# Carduino.net
KiCad netlist of a schematic drawn in Altium Designer
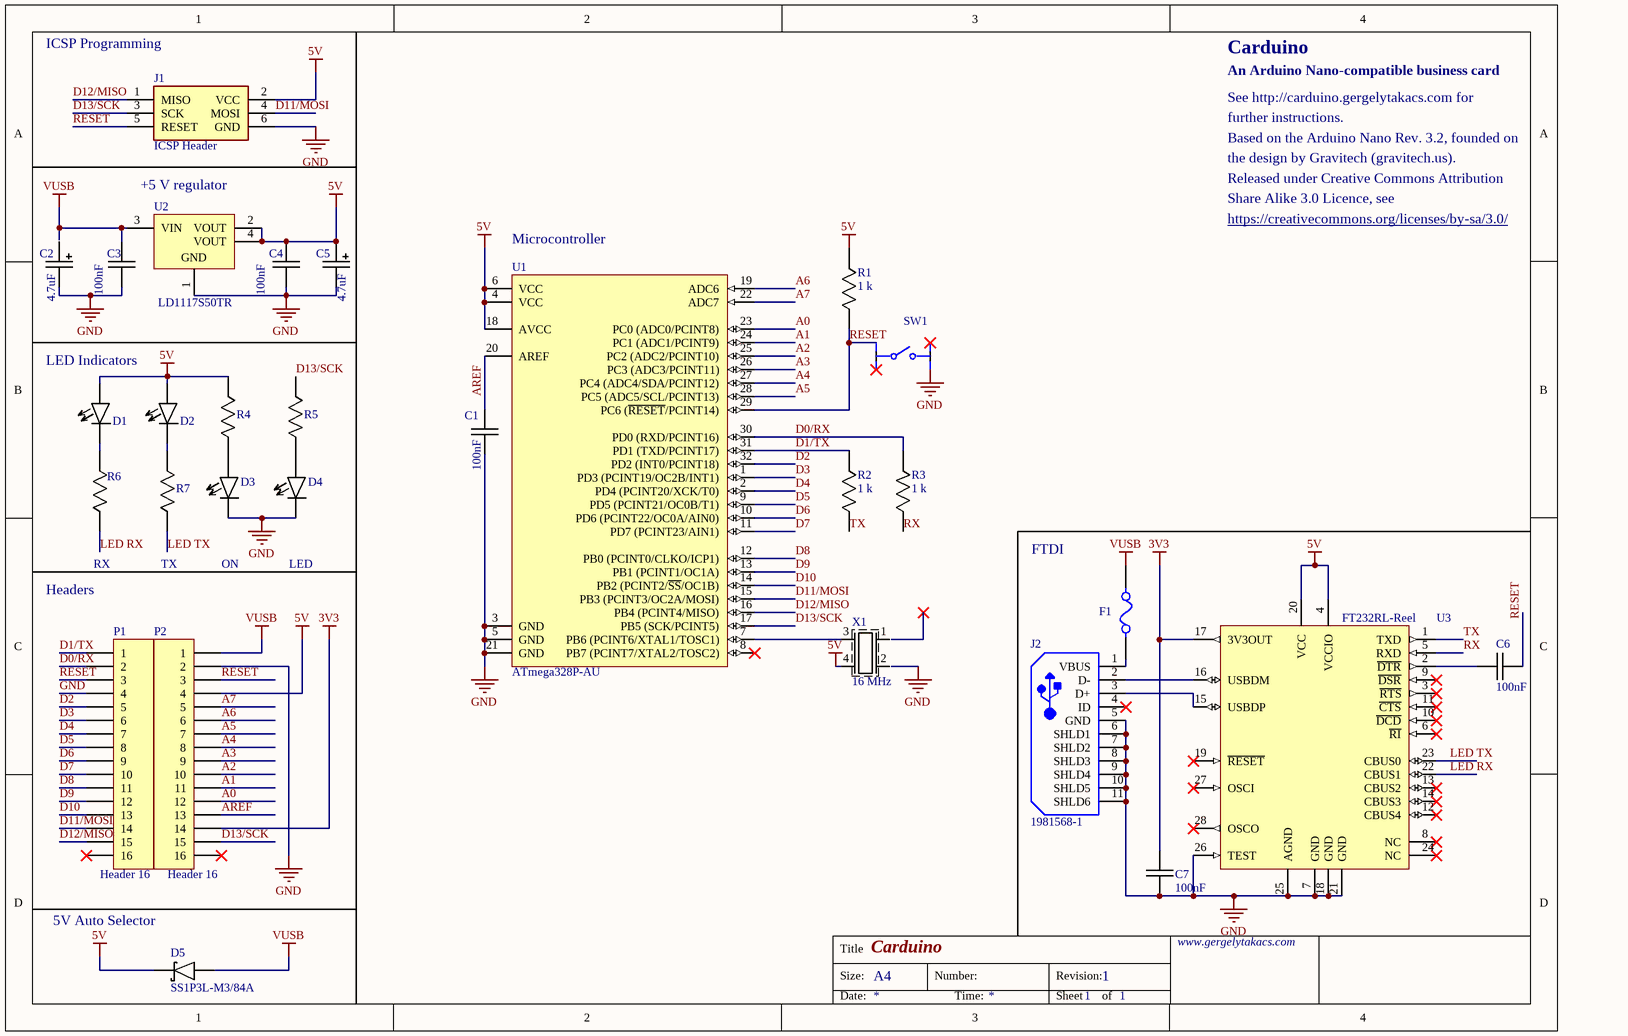
[diagram p0: Carduino.SchDoc]

(export (version "E")
  (design (tool "Eeschema 10.0.6"))
  (components
    (comp (ref "C1")
      (value "100nF")
      (footprint "CAPC2013X09N")
      (description "Ceramic condenser MLCC; 100nF; 25V; X7R; ±10%; SMD; 0805")
      (libsource (lib "Capacitors") (part "100 uF,  ceramic, 0805, Kemet"))
    )
    (comp (ref "C2")
      (value "4.7uF")
      (footprint "CAP body B")
      (description "4,7uF; 25VDC; SMD; Puzd: B; ±10%; -55÷125°C")
      (libsource (lib "Capacitors") (part "4.7uF, Tantallum"))
    )
    (comp (ref "C3")
      (value "100nF")
      (footprint "CAPC2013X09N")
      (description "Ceramic condenser MLCC; 100nF; 25V; X7R; ±10%; SMD; 0805")
      (libsource (lib "Capacitors") (part "100 uF,  ceramic, 0805, Kemet"))
    )
    (comp (ref "C4")
      (value "100nF")
      (footprint "CAPC2013X09N")
      (description "Ceramic condenser MLCC; 100nF; 25V; X7R; ±10%; SMD; 0805")
      (libsource (lib "Capacitors") (part "100 uF,  ceramic, 0805, Kemet"))
    )
    (comp (ref "C5")
      (value "4.7uF")
      (footprint "CAP body B")
      (description "4,7uF; 25VDC; SMD; Puzd: B; ±10%; -55÷125°C")
      (libsource (lib "Capacitors") (part "4.7uF, Tantallum"))
    )
    (comp (ref "C6")
      (value "100nF")
      (footprint "CAPC2013X09N")
      (description "Ceramic condenser MLCC; 100nF; 25V; X7R; ±10%; SMD; 0805")
      (libsource (lib "Capacitors") (part "100 uF,  ceramic, 0805, Kemet"))
    )
    (comp (ref "C7")
      (value "100nF")
      (footprint "CAPC2013X09N")
      (description "Ceramic condenser MLCC; 100nF; 25V; X7R; ±10%; SMD; 0805")
      (libsource (lib "Capacitors") (part "100 uF,  ceramic, 0805, Kemet"))
    )
    (comp (ref "D1")
      (value "OSXX0805C1E")
      (footprint "DIOC2012X09N")
      (description "OptoSupply Single Chip LED 0805")
      (fields
        (field (name "CREATOR") "Gergely Takacs")
        (field (name "CREATOR WWW") "http://www.gergelytakacs.com")
      )
      (libsource (lib "OptoSupplyLED") (part "OptoSupply RED"))
    )
    (comp (ref "D2")
      (value "OSXX0805C1E")
      (footprint "DIOC2012X09N")
      (description "OptoSupply Single Chip LED 0805")
      (fields
        (field (name "CREATOR") "Gergely Takacs")
        (field (name "CREATOR WWW") "http://www.gergelytakacs.com")
      )
      (libsource (lib "OptoSupplyLED") (part "OptoSupply RED"))
    )
    (comp (ref "D3")
      (value "OSXX0805C1E")
      (footprint "DIOC2012X09N")
      (description "OptoSupply Single Chip LED 0805")
      (fields
        (field (name "CREATOR") "Gergely Takacs")
        (field (name "CREATOR WWW") "http://www.gergelytakacs.com")
      )
      (libsource (lib "OptoSupplyLED") (part "OptoSupply RED"))
    )
    (comp (ref "D4")
      (value "OSXX0805C1E")
      (footprint "DIOC2012X09N")
      (description "OptoSupply Single Chip LED 0805")
      (fields
        (field (name "CREATOR") "Gergely Takacs")
        (field (name "CREATOR WWW") "http://www.gergelytakacs.com")
      )
      (libsource (lib "OptoSupplyLED") (part "OptoSupply RED"))
    )
    (comp (ref "D5")
      (value "SS1P3L-M3/84A")
      (footprint "DIOM3420X11N")
      (description "VISHAY SS1P3L-M3/84A  Dióda: usmerňovacia Schottky; SMD; 30V; 1A; DO220AA, SMP")
      (libsource (lib "Diodes") (part "SS1P3L"))
    )
    (comp (ref "F1")
      (value "ECE SR050-06")
      (footprint "RESC2113X12N")
      (description "FUSE PTC RESETTABLE .50A")
      (libsource (lib "Fuses") (part "ECE SR050-06"))
    )
    (comp (ref "J1")
      (value "Conn_3M_961206-6404-AR_eec")
      (footprint "3M_961206-6404-AR_0")
      (description "CONN HEADER VERT DUAL 6POS GOLD")
      (fields
        (field (name "MANUFACTURER") "3M")
        (field (name "MOUSER PART NUMBER") "517-9612066404AR")
        (field (name "PART NUMBER") "ICSP Header")
      )
      (libsource (lib "ICSP") (part "Conn_3M_961206-6404-AR_eec"))
    )
    (comp (ref "J2")
      (value "1981568-1")
      (footprint "TECO-1981568-5_V")
      (description "Micro USB Receptacle Standard Type B Assy, 5-Pin SMD, RoHS, Tape and Reel")
      (fields (field (name "MANUFACTURER") "TE Connectivity"))
      (libsource (lib "Connectors") (part "1981568-1"))
    )
    (comp (ref "P1")
      (value "Header 16")
      (footprint "HDR1X16")
      (description "Header, 16-Pin")
      (fields (field (name "PUBLISHER") "Altium Limited"))
      (libsource (lib "Miscellaneous Connectors") (part "Header 16"))
    )
    (comp (ref "P2")
      (value "Header 16")
      (footprint "HDR1X16")
      (description "Header, 16-Pin")
      (fields (field (name "PUBLISHER") "Altium Limited"))
      (libsource (lib "") (part "Header 16_1"))
    )
    (comp (ref "R1")
      (value "1 k")
      (footprint "RESC2112X05N")
      (description "ROYAL OHM HP05W3F1001T5E  Rezistor: thick film; vysokovýkonný; SMD; 0805; 1kΩ; 0,3W; ±1%")
      (libsource (lib "Resistors") (part "1k, 0805, Royal Ohm"))
    )
    (comp (ref "R2")
      (value "1 k")
      (footprint "RESC2112X05N")
      (description "ROYAL OHM HP05W3F1001T5E  Rezistor: thick film; vysokovýkonný; SMD; 0805; 1kΩ; 0,3W; ±1%")
      (libsource (lib "Resistors") (part "1k, 0805, Royal Ohm"))
    )
    (comp (ref "R3")
      (value "1 k")
      (footprint "RESC2112X05N")
      (description "ROYAL OHM HP05W3F1001T5E  Rezistor: thick film; vysokovýkonný; SMD; 0805; 1kΩ; 0,3W; ±1%")
      (libsource (lib "Resistors") (part "1k, 0805, Royal Ohm"))
    )
    (comp (ref "R4")
      (value "270 Ohm, 0805")
      (footprint "RESC2112X05N")
      (description "VISHAY CRCW...BC Thick Film Commodity Resistor")
      (libsource (lib "Vishay Resistors") (part "270 Ohm, 0805, Resistor"))
    )
    (comp (ref "R5")
      (value "270 Ohm, 0805")
      (footprint "RESC2112X05N")
      (description "VISHAY CRCW...BC Thick Film Commodity Resistor")
      (libsource (lib "Vishay Resistors") (part "270 Ohm, 0805, Resistor"))
    )
    (comp (ref "R6")
      (value "270 Ohm, 0805")
      (footprint "RESC2112X05N")
      (description "VISHAY CRCW...BC Thick Film Commodity Resistor")
      (libsource (lib "Vishay Resistors") (part "270 Ohm, 0805, Resistor"))
    )
    (comp (ref "R7")
      (value "270 Ohm, 0805")
      (footprint "RESC2112X05N")
      (description "VISHAY CRCW...BC Thick Film Commodity Resistor")
      (libsource (lib "Vishay Resistors") (part "270 Ohm, 0805, Resistor"))
    )
    (comp (ref "SW1")
      (value "Switch_TE_1825910-7_eec")
      (footprint "TE_1825910-7_0")
      (description "SWITCH Tactile Switch SPST-NO Top Actuated Through Hole")
      (fields (field (name "PART NUMBER") "1825910-7") (field (name "MANUFACTURER") "TE"))
      (libsource (lib "Switches") (part "Switch_TE_1825910-7_eec"))
    )
    (comp (ref "U1")
      (value "ATmega328P-AU")
      (footprint "32A_N")
      (libsource (lib "Atmel Microcontroller megaAVR") (part "ATmega328P-AU"))
    )
    (comp (ref "U2")
      (value "LD1117S50TR")
      (footprint "SOT-223_N")
      (description "Fixed Low Drop Positive Voltage Regulator, 5V, 4-Pin SOT-223, Tape and Reel")
      (libsource (lib "STMicroelectronics Power Management Linear Regulator") (part "LD1117S50TR"))
    )
    (comp (ref "U3")
      (value "FT232RL-Reel")
      (footprint "SSOP-28_N")
      (description "USB UART Asynchronous Serial Data Transfer Chip, 28-pin SSOP, Tape and Reel")
      (fields (field (name "MANUFACTURER") "FTDI"))
      (libsource (lib "FTDI FT Series") (part "FT232RL-Reel"))
    )
    (comp (ref "X1")
      (value "16 MHz")
      (footprint "DFN598P720X140-4N")
      (description "QD FREQUENCY PRODUCTS LF SPXO018034")
      (libsource (lib "Xtals") (part "16 MHz, IQD FREQUENCY PRODUCTS"))
    )
  )
  (nets
    (net (code "1") (name "/A0") (class "Default")
      (node (ref "P2") (pin "12") (pinfunction "12_12") (pintype "passive"))
      (node (ref "U1") (pin "23") (pinfunction "PC0_(ADC0/PCINT8)_23") (pintype "bidirectional"))
    )
    (net (code "2") (name "/A1") (class "Default")
      (node (ref "P2") (pin "11") (pinfunction "11_11") (pintype "passive"))
      (node (ref "U1") (pin "24") (pinfunction "PC1_(ADC1/PCINT9)_24") (pintype "bidirectional"))
    )
    (net (code "3") (name "/A2") (class "Default")
      (node (ref "P2") (pin "10") (pinfunction "10_10") (pintype "passive"))
      (node (ref "U1") (pin "25") (pinfunction "PC2_(ADC2/PCINT10)_25") (pintype "bidirectional"))
    )
    (net (code "4") (name "/A3") (class "Default")
      (node (ref "P2") (pin "9") (pinfunction "9_9") (pintype "passive"))
      (node (ref "U1") (pin "26") (pinfunction "PC3_(ADC3/PCINT11)_26") (pintype "bidirectional"))
    )
    (net (code "5") (name "/A4") (class "Default")
      (node (ref "P2") (pin "8") (pinfunction "8_8") (pintype "passive"))
      (node (ref "U1") (pin "27") (pinfunction "PC4_(ADC4/SDA/PCINT12)_27") (pintype "bidirectional"))
    )
    (net (code "6") (name "/A5") (class "Default")
      (node (ref "P2") (pin "7") (pinfunction "7_7") (pintype "passive"))
      (node (ref "U1") (pin "28") (pinfunction "PC5_(ADC5/SCL/PCINT13)_28") (pintype "bidirectional"))
    )
    (net (code "7") (name "/A6") (class "Default")
      (node (ref "P2") (pin "6") (pinfunction "6_6") (pintype "passive"))
      (node (ref "U1") (pin "19") (pinfunction "ADC6_19") (pintype "input"))
    )
    (net (code "8") (name "/A7") (class "Default")
      (node (ref "P2") (pin "5") (pinfunction "5_5") (pintype "passive"))
      (node (ref "U1") (pin "22") (pinfunction "ADC7_22") (pintype "input"))
    )
    (net (code "9") (name "/AREF") (class "Default")
      (node (ref "C1") (pin "1") (pinfunction "1_1") (pintype "passive"))
      (node (ref "P2") (pin "13") (pinfunction "13_13") (pintype "passive"))
      (node (ref "U1") (pin "20") (pinfunction "AREF_20") (pintype "passive"))
    )
    (net (code "10") (name "/D0{slash}RX") (class "Default")
      (node (ref "P1") (pin "2") (pinfunction "2_2") (pintype "passive"))
      (node (ref "R3") (pin "2") (pinfunction "2_2") (pintype "passive"))
      (node (ref "U1") (pin "30") (pinfunction "PD0_(RXD/PCINT16)_30") (pintype "bidirectional"))
    )
    (net (code "11") (name "/D1{slash}TX") (class "Default")
      (node (ref "P1") (pin "1") (pinfunction "1_1") (pintype "passive"))
      (node (ref "R2") (pin "1") (pinfunction "1_1") (pintype "passive"))
      (node (ref "U1") (pin "31") (pinfunction "PD1_(TXD/PCINT17)_31") (pintype "bidirectional"))
    )
    (net (code "12") (name "/D2") (class "Default")
      (node (ref "P1") (pin "5") (pinfunction "5_5") (pintype "passive"))
      (node (ref "U1") (pin "32") (pinfunction "PD2_(INT0/PCINT18)_32") (pintype "bidirectional"))
    )
    (net (code "13") (name "/D3") (class "Default")
      (node (ref "P1") (pin "6") (pinfunction "6_6") (pintype "passive"))
      (node (ref "U1") (pin "1") (pinfunction "PD3_(PCINT19/OC2B/INT1)_1") (pintype "bidirectional"))
    )
    (net (code "14") (name "/D4") (class "Default")
      (node (ref "P1") (pin "7") (pinfunction "7_7") (pintype "passive"))
      (node (ref "U1") (pin "2") (pinfunction "PD4_(PCINT20/XCK/T0)_2") (pintype "bidirectional"))
    )
    (net (code "15") (name "/D5") (class "Default")
      (node (ref "P1") (pin "8") (pinfunction "8_8") (pintype "passive"))
      (node (ref "U1") (pin "9") (pinfunction "PD5_(PCINT21/OC0B/T1)_9") (pintype "bidirectional"))
    )
    (net (code "16") (name "/D6") (class "Default")
      (node (ref "P1") (pin "9") (pinfunction "9_9") (pintype "passive"))
      (node (ref "U1") (pin "10") (pinfunction "PD6_(PCINT22/OC0A/AIN0)_10") (pintype "bidirectional"))
    )
    (net (code "17") (name "/D7") (class "Default")
      (node (ref "P1") (pin "10") (pinfunction "10_10") (pintype "passive"))
      (node (ref "U1") (pin "11") (pinfunction "PD7_(PCINT23/AIN1)_11") (pintype "bidirectional"))
    )
    (net (code "18") (name "/D8") (class "Default")
      (node (ref "P1") (pin "11") (pinfunction "11_11") (pintype "passive"))
      (node (ref "U1") (pin "12") (pinfunction "PB0_(PCINT0/CLKO/ICP1)_12") (pintype "bidirectional"))
    )
    (net (code "19") (name "/D9") (class "Default")
      (node (ref "P1") (pin "12") (pinfunction "12_12") (pintype "passive"))
      (node (ref "U1") (pin "13") (pinfunction "PB1_(PCINT1/OC1A)_13") (pintype "bidirectional"))
    )
    (net (code "20") (name "/D10") (class "Default")
      (node (ref "P1") (pin "13") (pinfunction "13_13") (pintype "passive"))
      (node (ref "U1") (pin "14") (pinfunction "PB2_(PCINT2/~{SS}/OC1B)_14") (pintype "bidirectional"))
    )
    (net (code "21") (name "/D11{slash}MOSI") (class "Default")
      (node (ref "J1") (pin "4") (pinfunction "MOSI_4") (pintype "passive"))
      (node (ref "P1") (pin "14") (pinfunction "14_14") (pintype "passive"))
      (node (ref "U1") (pin "15") (pinfunction "PB3_(PCINT3/OC2A/MOSI)_15") (pintype "bidirectional"))
    )
    (net (code "22") (name "/D12{slash}MISO") (class "Default")
      (node (ref "J1") (pin "1") (pinfunction "MISO_1") (pintype "passive"))
      (node (ref "P1") (pin "15") (pinfunction "15_15") (pintype "passive"))
      (node (ref "U1") (pin "16") (pinfunction "PB4_(PCINT4/MISO)_16") (pintype "bidirectional"))
    )
    (net (code "23") (name "/D13{slash}SCK") (class "Default")
      (node (ref "J1") (pin "3") (pinfunction "SCK_3") (pintype "passive"))
      (node (ref "P2") (pin "15") (pinfunction "15_15") (pintype "passive"))
      (node (ref "R5") (pin "1") (pinfunction "1_1") (pintype "passive"))
      (node (ref "U1") (pin "17") (pinfunction "PB5_(SCK/PCINT5)_17") (pintype "bidirectional"))
    )
    (net (code "24") (name "/LED RX") (class "Default")
      (node (ref "R6") (pin "2") (pinfunction "2_2") (pintype "passive"))
      (node (ref "U3") (pin "22") (pinfunction "CBUS1_22") (pintype "bidirectional"))
    )
    (net (code "25") (name "/LED TX") (class "Default")
      (node (ref "R7") (pin "2") (pinfunction "2_2") (pintype "passive"))
      (node (ref "U3") (pin "23") (pinfunction "CBUS0_23") (pintype "bidirectional"))
    )
    (net (code "26") (name "/RESET") (class "Default")
      (node (ref "C6") (pin "2") (pinfunction "2_2") (pintype "passive"))
      (node (ref "J1") (pin "5") (pinfunction "RESET_5") (pintype "passive"))
      (node (ref "P1") (pin "3") (pinfunction "3_3") (pintype "passive"))
      (node (ref "P2") (pin "3") (pinfunction "3_3") (pintype "passive"))
      (node (ref "R1") (pin "2") (pinfunction "2_2") (pintype "passive"))
      (node (ref "SW1") (pin "1") (pinfunction "1_1") (pintype "passive"))
      (node (ref "U1") (pin "29") (pinfunction "PC6_(~{RESET}/PCINT14)_29") (pintype "bidirectional"))
    )
    (net (code "27") (name "/RX") (class "Default")
      (node (ref "R3") (pin "1") (pinfunction "1_1") (pintype "passive"))
      (node (ref "U3") (pin "5") (pinfunction "RXD_5") (pintype "input"))
    )
    (net (code "28") (name "/TX") (class "Default")
      (node (ref "R2") (pin "2") (pinfunction "2_2") (pintype "passive"))
      (node (ref "U3") (pin "1") (pinfunction "TXD_1") (pintype "output"))
    )
    (net (code "29") (name "3V3") (class "Default")
      (node (ref "C7") (pin "2") (pinfunction "2_2") (pintype "passive"))
      (node (ref "P2") (pin "14") (pinfunction "14_14") (pintype "passive"))
      (node (ref "U3") (pin "17") (pinfunction "3V3OUT_17") (pintype "output"))
    )
    (net (code "30") (name "5V") (class "Default")
      (node (ref "C4") (pin "1") (pinfunction "1_1") (pintype "passive"))
      (node (ref "C5") (pin "1") (pinfunction "1_1") (pintype "passive"))
      (node (ref "D1") (pin "2") (pinfunction "2_2") (pintype "passive"))
      (node (ref "D2") (pin "2") (pinfunction "2_2") (pintype "passive"))
      (node (ref "D5") (pin "1") (pinfunction "1_1") (pintype "passive"))
      (node (ref "J1") (pin "2") (pinfunction "VCC_2") (pintype "passive"))
      (node (ref "P2") (pin "4") (pinfunction "4_4") (pintype "passive"))
      (node (ref "R1") (pin "1") (pinfunction "1_1") (pintype "passive"))
      (node (ref "R4") (pin "1") (pinfunction "1_1") (pintype "passive"))
      (node (ref "U1") (pin "18") (pinfunction "AVCC_18") (pintype "power_in"))
      (node (ref "U1") (pin "4") (pinfunction "VCC_4") (pintype "power_in"))
      (node (ref "U1") (pin "6") (pinfunction "VCC_6") (pintype "power_in"))
      (node (ref "U2") (pin "2") (pinfunction "VOUT_2") (pintype "power_in"))
      (node (ref "U2") (pin "4") (pinfunction "VOUT_4") (pintype "power_in"))
      (node (ref "U3") (pin "20") (pinfunction "VCC_20") (pintype "power_in"))
      (node (ref "U3") (pin "4") (pinfunction "VCCIO_4") (pintype "power_in"))
      (node (ref "X1") (pin "4") (pinfunction "4_4") (pintype "passive"))
    )
    (net (code "31") (name "GND") (class "Default")
      (node (ref "C1") (pin "2") (pinfunction "2_2") (pintype "passive"))
      (node (ref "C2") (pin "2") (pinfunction "2_2") (pintype "passive"))
      (node (ref "C3") (pin "1") (pinfunction "1_1") (pintype "passive"))
      (node (ref "C4") (pin "2") (pinfunction "2_2") (pintype "passive"))
      (node (ref "C5") (pin "2") (pinfunction "2_2") (pintype "passive"))
      (node (ref "C7") (pin "1") (pinfunction "1_1") (pintype "passive"))
      (node (ref "D3") (pin "1") (pinfunction "1_1") (pintype "passive"))
      (node (ref "D4") (pin "1") (pinfunction "1_1") (pintype "passive"))
      (node (ref "J1") (pin "6") (pinfunction "GND_6") (pintype "passive"))
      (node (ref "J2") (pin "10") (pinfunction "SHLD5_10") (pintype "passive"))
      (node (ref "J2") (pin "11") (pinfunction "SHLD6_11") (pintype "passive"))
      (node (ref "J2") (pin "5") (pinfunction "GND_5") (pintype "passive"))
      (node (ref "J2") (pin "6") (pinfunction "SHLD1_6") (pintype "passive"))
      (node (ref "J2") (pin "7") (pinfunction "SHLD2_7") (pintype "passive"))
      (node (ref "J2") (pin "8") (pinfunction "SHLD3_8") (pintype "passive"))
      (node (ref "J2") (pin "9") (pinfunction "SHLD4_9") (pintype "passive"))
      (node (ref "P1") (pin "4") (pinfunction "4_4") (pintype "passive"))
      (node (ref "P2") (pin "2") (pinfunction "2_2") (pintype "passive"))
      (node (ref "SW1") (pin "4") (pinfunction "4_4") (pintype "passive"))
      (node (ref "U1") (pin "21") (pinfunction "GND_21") (pintype "power_in"))
      (node (ref "U1") (pin "3") (pinfunction "GND_3") (pintype "power_in"))
      (node (ref "U1") (pin "5") (pinfunction "GND_5") (pintype "power_in"))
      (node (ref "U2") (pin "1") (pinfunction "GND_1") (pintype "power_in"))
      (node (ref "U3") (pin "18") (pinfunction "GND_18") (pintype "power_in"))
      (node (ref "U3") (pin "21") (pinfunction "GND_21") (pintype "power_in"))
      (node (ref "U3") (pin "25") (pinfunction "AGND_25") (pintype "power_in"))
      (node (ref "U3") (pin "26") (pinfunction "TEST_26") (pintype "input"))
      (node (ref "U3") (pin "7") (pinfunction "GND_7") (pintype "power_in"))
    )
    (net (code "32") (name "Net-(D1-Pad1)") (class "Default")
      (node (ref "D1") (pin "1") (pinfunction "1_1") (pintype "passive"))
      (node (ref "R6") (pin "1") (pinfunction "1_1") (pintype "passive"))
    )
    (net (code "33") (name "Net-(D2-Pad1)") (class "Default")
      (node (ref "D2") (pin "1") (pinfunction "1_1") (pintype "passive"))
      (node (ref "R7") (pin "1") (pinfunction "1_1") (pintype "passive"))
    )
    (net (code "34") (name "Net-(D3-Pad2)") (class "Default")
      (node (ref "D3") (pin "2") (pinfunction "2_2") (pintype "passive"))
      (node (ref "R4") (pin "2") (pinfunction "2_2") (pintype "passive"))
    )
    (net (code "35") (name "Net-(D4-Pad2)") (class "Default")
      (node (ref "D4") (pin "2") (pinfunction "2_2") (pintype "passive"))
      (node (ref "R5") (pin "2") (pinfunction "2_2") (pintype "passive"))
    )
    (net (code "36") (name "Net-(J2-D+)") (class "Default")
      (node (ref "J2") (pin "3") (pinfunction "D+_3") (pintype "passive"))
      (node (ref "U3") (pin "15") (pinfunction "USBDP_15") (pintype "bidirectional"))
    )
    (net (code "37") (name "Net-(J2-D-)") (class "Default")
      (node (ref "J2") (pin "2") (pinfunction "D-_2") (pintype "passive"))
      (node (ref "U3") (pin "16") (pinfunction "USBDM_16") (pintype "bidirectional"))
    )
    (net (code "38") (name "Net-(J2-VBUS)") (class "Default")
      (node (ref "F1") (pin "1") (pinfunction "1_1") (pintype "passive"))
      (node (ref "J2") (pin "1") (pinfunction "VBUS_1") (pintype "passive"))
    )
    (net (code "39") (name "Net-(U1-PB6_(PCINT6{slash}XTAL1{slash}TOSC1))") (class "Default")
      (node (ref "U1") (pin "7") (pinfunction "PB6_(PCINT6/XTAL1/TOSC1)_7") (pintype "bidirectional"))
      (node (ref "X1") (pin "3") (pinfunction "3_3") (pintype "passive"))
    )
    (net (code "40") (name "Net-(U3-~{DTR})") (class "Default")
      (node (ref "C6") (pin "1") (pinfunction "1_1") (pintype "passive"))
      (node (ref "U3") (pin "2") (pinfunction "~{DTR}_2") (pintype "output"))
    )
    (net (code "41") (name "VUSB") (class "Default")
      (node (ref "C3") (pin "2") (pinfunction "2_2") (pintype "passive"))
      (node (ref "D5") (pin "2") (pinfunction "2_2") (pintype "passive"))
      (node (ref "F1") (pin "2") (pinfunction "2_2") (pintype "passive"))
      (node (ref "P2") (pin "1") (pinfunction "1_1") (pintype "passive"))
      (node (ref "U2") (pin "3") (pinfunction "VIN_3") (pintype "power_in"))
    )
    (net (code "42") (name "unconnected-(C2-Pad1)") (class "Default")
      (node (ref "C2") (pin "1") (pinfunction "1_1") (pintype "passive"))
    )
    (net (code "43") (name "unconnected-(J2-ID-Pad4)") (class "Default")
      (node (ref "J2") (pin "4") (pinfunction "ID_4") (pintype "passive+no_connect"))
    )
    (net (code "44") (name "unconnected-(P1-Pad16)") (class "Default")
      (node (ref "P1") (pin "16") (pinfunction "16_16") (pintype "passive+no_connect"))
    )
    (net (code "45") (name "unconnected-(P2-Pad16)") (class "Default")
      (node (ref "P2") (pin "16") (pinfunction "16_16") (pintype "passive+no_connect"))
    )
    (net (code "46") (name "unconnected-(SW1-Pad2)") (class "Default")
      (node (ref "SW1") (pin "2") (pinfunction "2_2") (pintype "passive+no_connect"))
    )
    (net (code "47") (name "unconnected-(SW1-Pad3)") (class "Default")
      (node (ref "SW1") (pin "3") (pinfunction "3_3") (pintype "passive+no_connect"))
    )
    (net (code "48") (name "unconnected-(U1-PB7_(PCINT7{slash}XTAL2{slash}TOSC2)-Pad8)") (class "Default")
      (node (ref "U1") (pin "8") (pinfunction "PB7_(PCINT7/XTAL2/TOSC2)_8") (pintype "bidirectional+no_connect"))
    )
    (net (code "49") (name "unconnected-(U3-CBUS2-Pad13)") (class "Default")
      (node (ref "U3") (pin "13") (pinfunction "CBUS2_13") (pintype "bidirectional+no_connect"))
    )
    (net (code "50") (name "unconnected-(U3-CBUS3-Pad14)") (class "Default")
      (node (ref "U3") (pin "14") (pinfunction "CBUS3_14") (pintype "bidirectional+no_connect"))
    )
    (net (code "51") (name "unconnected-(U3-CBUS4-Pad12)") (class "Default")
      (node (ref "U3") (pin "12") (pinfunction "CBUS4_12") (pintype "bidirectional+no_connect"))
    )
    (net (code "52") (name "unconnected-(U3-NC-Pad8)") (class "Default")
      (node (ref "U3") (pin "8") (pinfunction "NC_8") (pintype "passive+no_connect"))
    )
    (net (code "53") (name "unconnected-(U3-NC-Pad24)") (class "Default")
      (node (ref "U3") (pin "24") (pinfunction "NC_24") (pintype "passive+no_connect"))
    )
    (net (code "54") (name "unconnected-(U3-OSCI-Pad27)") (class "Default")
      (node (ref "U3") (pin "27") (pinfunction "OSCI_27") (pintype "input+no_connect"))
    )
    (net (code "55") (name "unconnected-(U3-OSCO-Pad28)") (class "Default")
      (node (ref "U3") (pin "28") (pinfunction "OSCO_28") (pintype "output+no_connect"))
    )
    (net (code "56") (name "unconnected-(U3-~{CTS}-Pad11)") (class "Default")
      (node (ref "U3") (pin "11") (pinfunction "~{CTS}_11") (pintype "input+no_connect"))
    )
    (net (code "57") (name "unconnected-(U3-~{DCD}-Pad10)") (class "Default")
      (node (ref "U3") (pin "10") (pinfunction "~{DCD}_10") (pintype "input+no_connect"))
    )
    (net (code "58") (name "unconnected-(U3-~{DSR}-Pad9)") (class "Default")
      (node (ref "U3") (pin "9") (pinfunction "~{DSR}_9") (pintype "input+no_connect"))
    )
    (net (code "59") (name "unconnected-(U3-~{RESET}-Pad19)") (class "Default")
      (node (ref "U3") (pin "19") (pinfunction "~{RESET}_19") (pintype "input+no_connect"))
    )
    (net (code "60") (name "unconnected-(U3-~{RI}-Pad6)") (class "Default")
      (node (ref "U3") (pin "6") (pinfunction "~{RI}_6") (pintype "input+no_connect"))
    )
    (net (code "61") (name "unconnected-(U3-~{RTS}-Pad3)") (class "Default")
      (node (ref "U3") (pin "3") (pinfunction "~{RTS}_3") (pintype "output+no_connect"))
    )
    (net (code "62") (name "unconnected-(X1-Pad1)") (class "Default")
      (node (ref "X1") (pin "1") (pinfunction "1_1") (pintype "passive"))
    )
    (net (code "63") (name "unconnected-(X1-Pad2)") (class "Default")
      (node (ref "X1") (pin "2") (pinfunction "2_2") (pintype "passive"))
    )
  )
)
